# CH32V103R-R1.net
KiCad netlist of a schematic drawn in Altium Designer
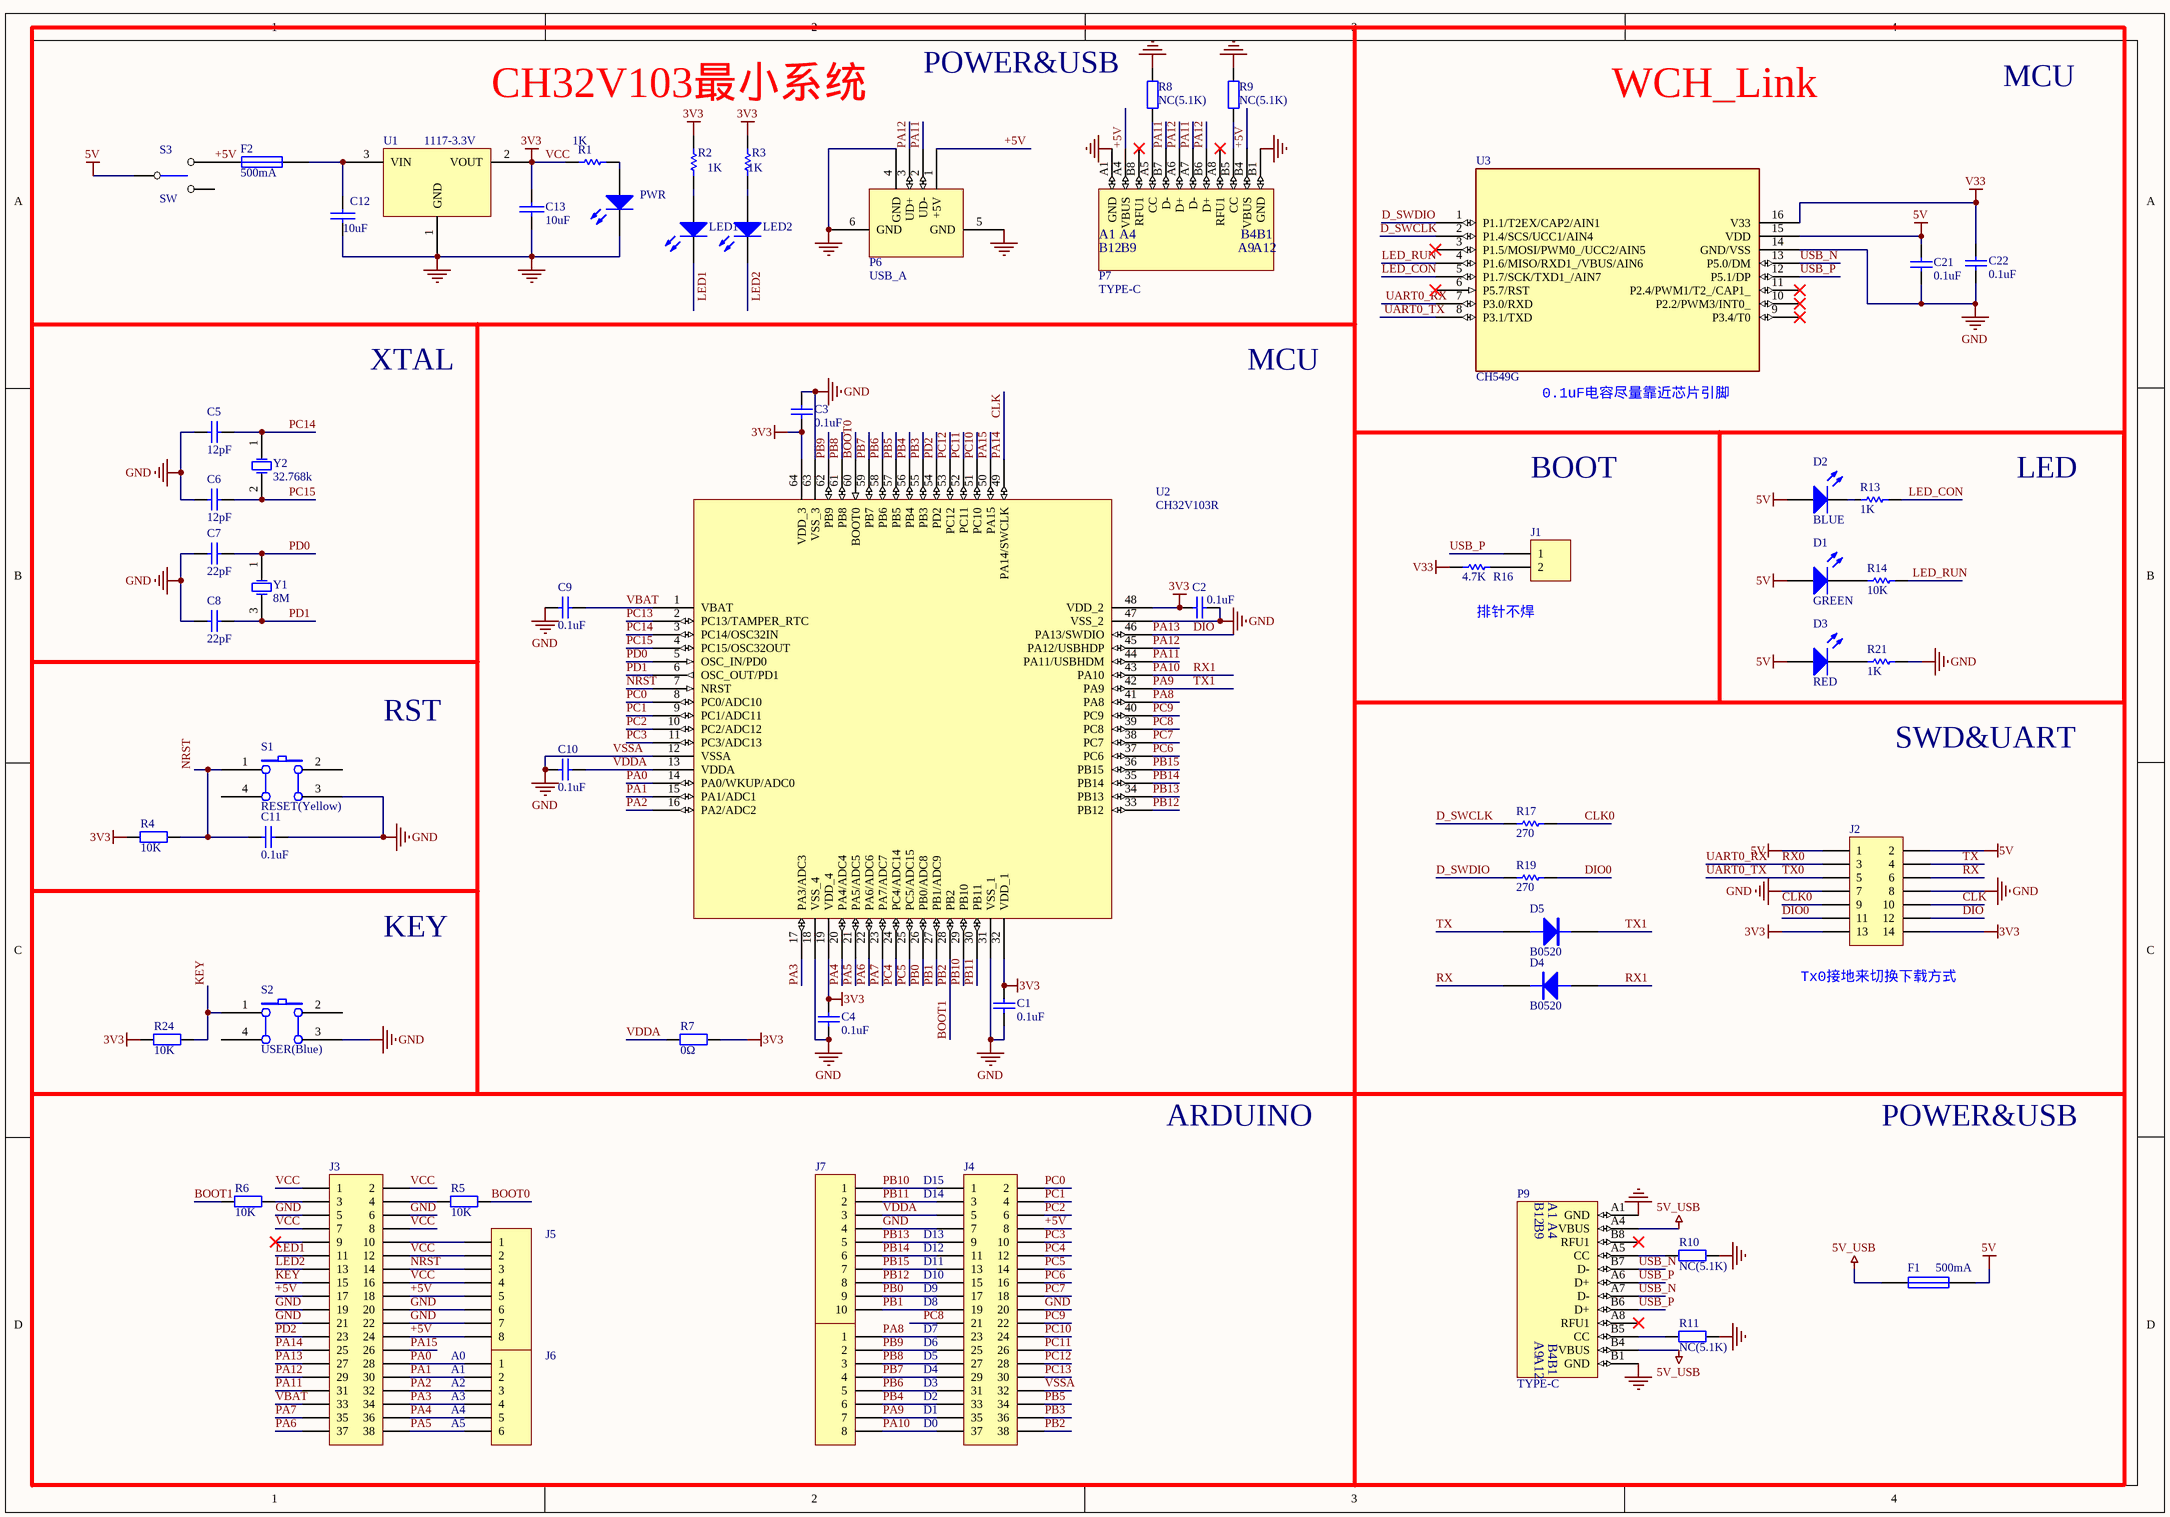
[diagram p0: CH32V103R-R1.SchDoc]

(export (version "E")
  (design (tool "Eeschema 10.0.6"))
  (components
    (comp (ref "C1")
      (value "0.1uF")
      (footprint "0603_C")
      (description "Capacitor")
      (libsource (lib "Miscellaneous Devices") (part "Cap"))
    )
    (comp (ref "C2")
      (value "0.1uF")
      (footprint "0603_C")
      (description "Capacitor")
      (libsource (lib "Miscellaneous Devices") (part "Cap"))
    )
    (comp (ref "C3")
      (value "0.1uF")
      (footprint "0603_C")
      (description "Capacitor")
      (libsource (lib "Miscellaneous Devices") (part "Cap"))
    )
    (comp (ref "C4")
      (value "0.1uF")
      (footprint "0603_C")
      (description "Capacitor")
      (libsource (lib "Miscellaneous Devices") (part "Cap"))
    )
    (comp (ref "C5")
      (value "12pF")
      (footprint "0603_C")
      (description "Capacitor")
      (libsource (lib "Miscellaneous Devices") (part "Cap"))
    )
    (comp (ref "C6")
      (value "12pF")
      (footprint "0603_C")
      (description "Capacitor")
      (libsource (lib "Miscellaneous Devices") (part "Cap"))
    )
    (comp (ref "C7")
      (value "22pF")
      (footprint "0603_C")
      (description "Capacitor")
      (libsource (lib "Miscellaneous Devices") (part "Cap"))
    )
    (comp (ref "C8")
      (value "22pF")
      (footprint "0603_C")
      (description "Capacitor")
      (libsource (lib "Miscellaneous Devices") (part "Cap"))
    )
    (comp (ref "C9")
      (value "0.1uF")
      (footprint "0603_C")
      (description "Capacitor")
      (libsource (lib "Miscellaneous Devices") (part "Cap"))
    )
    (comp (ref "C10")
      (value "0.1uF")
      (footprint "0603_C")
      (description "Capacitor")
      (libsource (lib "Miscellaneous Devices") (part "Cap"))
    )
    (comp (ref "C11")
      (value "0.1uF")
      (footprint "0603_C")
      (description "Capacitor")
      (libsource (lib "Miscellaneous Devices") (part "Cap"))
    )
    (comp (ref "C12")
      (value "10uF")
      (footprint "3216_C")
      (description "Capacitor")
      (libsource (lib "*") (part "CAP"))
    )
    (comp (ref "C13")
      (value "10uF")
      (footprint "0603_C")
      (description "Capacitor")
      (libsource (lib "*") (part "CAP"))
    )
    (comp (ref "C21")
      (value "0.1uF")
      (footprint "0603_C")
      (description "Capacitor")
      (fields (field (name "PUBLISHER") "Altium Limited"))
      (libsource (lib "MYLIB") (part "C-RAD-0603"))
    )
    (comp (ref "C22")
      (value "0.1uF")
      (footprint "0603_C")
      (description "Capacitor")
      (fields (field (name "PUBLISHER") "Altium Limited"))
      (libsource (lib "MYLIB") (part "C-RAD-0603"))
    )
    (comp (ref "D1")
      (value "GREEN")
      (footprint "0603+")
      (description "Typical RED, GREEN, YELLOW, AMBER GaAs LED")
      (fields (field (name "PUBLISHER") "Altium Limited"))
      (libsource (lib "MYLIB") (part "D0603"))
    )
    (comp (ref "D2")
      (value "BLUE")
      (footprint "0603+")
      (description "Typical RED, GREEN, YELLOW, AMBER GaAs LED")
      (fields (field (name "PUBLISHER") "Altium Limited"))
      (libsource (lib "MYLIB") (part "D0603"))
    )
    (comp (ref "D3")
      (value "RED")
      (footprint "0603+")
      (description "Typical RED, GREEN, YELLOW, AMBER GaAs LED")
      (fields (field (name "PUBLISHER") "Altium Limited"))
      (libsource (lib "MYLIB") (part "D0603"))
    )
    (comp (ref "D4")
      (value "B0520")
      (footprint "SOD-323")
      (description "Diode")
      (libsource (lib "*") (part "DIODE"))
    )
    (comp (ref "D5")
      (value "B0520")
      (footprint "SOD-323")
      (description "Diode")
      (libsource (lib "*") (part "DIODE"))
    )
    (comp (ref "F1")
      (value "500mA")
      (footprint "0805")
      (description "Fuse")
      (libsource (lib "*") (part "FUSE1"))
    )
    (comp (ref "F2")
      (value "500mA")
      (footprint "0805")
      (description "Fuse")
      (libsource (lib "*") (part "FUSE1"))
    )
    (comp (ref "J1")
      (value "Header 2")
      (footprint "SIP2-2.54MM")
      (description "Header, 2-Pin")
      (fields (field (name "PUBLISHER") "Altium Limited"))
      (libsource (lib "Miscellaneous Connectors") (part "Header 2"))
    )
    (comp (ref "J2")
      (value "Header 7X2")
      (footprint "IDC14-2.54mm")
      (description "Header, 7-Pin, Dual row")
      (fields (field (name "PUBLISHER") "Altium Limited"))
      (libsource (lib "Miscellaneous Connectors") (part "Header 7X2"))
    )
    (comp (ref "J3")
      (value "Header 19X2")
      (footprint "IDC38-2.54mm")
      (description "Header, 19-Pin, Dual row")
      (fields (field (name "PUBLISHER") "Altium Limited"))
      (libsource (lib "Miscellaneous Connectors") (part "Header 19X2"))
    )
    (comp (ref "J4")
      (value "Header 19X2")
      (footprint "IDC38-2.54mm")
      (description "Header, 19-Pin, Dual row")
      (fields (field (name "PUBLISHER") "Altium Limited"))
      (libsource (lib "Miscellaneous Connectors") (part "Header 19X2"))
    )
    (comp (ref "J5")
      (value "Header 8")
      (footprint "SIP8-2.54mm")
      (description "Header, 8-Pin")
      (fields (field (name "PUBLISHER") "Altium Limited"))
      (libsource (lib "Miscellaneous Connectors") (part "Header 8"))
    )
    (comp (ref "J6")
      (value "Header 6")
      (footprint "SIP6-2.54MM")
      (description "Header, 6-Pin")
      (fields (field (name "PUBLISHER") "Altium Limited"))
      (libsource (lib "Miscellaneous Connectors") (part "Header 6"))
    )
    (comp (ref "J7")
      (value "Header 10")
      (footprint "SIP10-2.54mm")
      (description "Header, 10-Pin")
      (fields (field (name "PUBLISHER") "Altium Limited"))
      (libsource (lib "Miscellaneous Connectors") (part "Header 10"))
    )
    (comp (ref "J8")
      (value "Header 8")
      (footprint "SIP8-2.54mm")
      (description "Header, 8-Pin")
      (fields (field (name "PUBLISHER") "Altium Limited"))
      (libsource (lib "") (part "Header 8_1"))
    )
    (comp (ref "LED1")
      (value "LED1   blue")
      (footprint "0603+")
      (description "Typical INFRARED GaAs LED")
      (fields (field (name "PUBLISHER") "Altium Limited"))
      (libsource (lib "Miscellaneous Devices") (part "LED0"))
    )
    (comp (ref "LED2")
      (value "LED2  blue")
      (footprint "0603+")
      (description "Typical INFRARED GaAs LED")
      (fields (field (name "PUBLISHER") "Altium Limited"))
      (libsource (lib "Miscellaneous Devices") (part "LED0"))
    )
    (comp (ref "P6")
      (value "USB_A")
      (footprint "USBAF")
      (description "USB Port")
      (libsource (lib "CHXXXSCH") (part "USB"))
    )
    (comp (ref "P7")
      (value "TYPE-C")
      (footprint "TYPE-C-Receptacle-2.0")
      (libsource (lib "*") (part "TYPE-C1"))
    )
    (comp (ref "P9")
      (value "TYPE-C")
      (footprint "TYPE-C-Receptacle-2.0")
      (libsource (lib "") (part "TYPE-C1_1"))
    )
    (comp (ref "PWR")
      (value "POWER  red")
      (footprint "0603+")
      (description "Typical INFRARED GaAs LED")
      (fields (field (name "PUBLISHER") "Altium Limited"))
      (libsource (lib "Miscellaneous Devices") (part "LED0"))
    )
    (comp (ref "R1")
      (value "1K")
      (footprint "0603")
      (description "Semiconductor Resistor")
      (libsource (lib "Miscellaneous Devices") (part "Res Semi"))
    )
    (comp (ref "R2")
      (value "1K")
      (footprint "0603")
      (description "Semiconductor Resistor")
      (libsource (lib "Miscellaneous Devices") (part "Res Semi"))
    )
    (comp (ref "R3")
      (value "1K")
      (footprint "0603")
      (description "Semiconductor Resistor")
      (libsource (lib "Miscellaneous Devices") (part "Res Semi"))
    )
    (comp (ref "R4")
      (value "10K")
      (footprint "0603")
      (description "Resistor")
      (libsource (lib "Miscellaneous Devices") (part "Res2"))
    )
    (comp (ref "R5")
      (value "10K")
      (footprint "0603")
      (description "Resistor")
      (libsource (lib "") (part "Res2_1"))
    )
    (comp (ref "R6")
      (value "10K")
      (footprint "0603")
      (description "Resistor")
      (libsource (lib "") (part "Res2_1"))
    )
    (comp (ref "R7")
      (value "0Ω")
      (footprint "0603")
      (description "Resistor")
      (libsource (lib "Miscellaneous Devices") (part "Res2"))
    )
    (comp (ref "R8")
      (value "NC(5.1K)")
      (footprint "0603")
      (description "Resistor")
      (libsource (lib "") (part "Res2_2"))
    )
    (comp (ref "R9")
      (value "NC(5.1K)")
      (footprint "0603")
      (description "Resistor")
      (libsource (lib "") (part "Res2_2"))
    )
    (comp (ref "R10")
      (value "NC(5.1K)")
      (footprint "0603")
      (description "Resistor")
      (libsource (lib "") (part "Res2_1"))
    )
    (comp (ref "R11")
      (value "NC(5.1K)")
      (footprint "0603")
      (description "Resistor")
      (libsource (lib "") (part "Res2_1"))
    )
    (comp (ref "R13")
      (value "1K")
      (footprint "0603")
      (description "Resistor")
      (fields (field (name "PUBLISHER") "Altium Limited"))
      (libsource (lib "MYLIB") (part "0603-1"))
    )
    (comp (ref "R14")
      (value "10K")
      (footprint "0603")
      (description "Resistor")
      (fields (field (name "PUBLISHER") "Altium Limited"))
      (libsource (lib "MYLIB") (part "0603-1"))
    )
    (comp (ref "R16")
      (value "4.7K")
      (footprint "0603")
      (description "Resistor")
      (fields (field (name "PUBLISHER") "Altium Limited"))
      (libsource (lib "MYLIB") (part "0603-1"))
    )
    (comp (ref "R17")
      (value "270")
      (footprint "0603")
      (description "Resistor")
      (fields (field (name "PUBLISHER") "Altium Limited"))
      (libsource (lib "MYLIB") (part "0603-1"))
    )
    (comp (ref "R19")
      (value "270")
      (footprint "0603")
      (description "Resistor")
      (fields (field (name "PUBLISHER") "Altium Limited"))
      (libsource (lib "MYLIB") (part "0603-1"))
    )
    (comp (ref "R21")
      (value "1K")
      (footprint "0603")
      (description "Resistor")
      (fields (field (name "PUBLISHER") "Altium Limited"))
      (libsource (lib "MYLIB") (part "0603-1"))
    )
    (comp (ref "R24")
      (value "10K")
      (footprint "0603")
      (description "Resistor")
      (libsource (lib "Miscellaneous Devices") (part "Res2"))
    )
    (comp (ref "S1")
      (value "RESET(Yellow)")
      (footprint "KEYX")
      (description "SE PUSHBUTTON")
      (libsource (lib "Documents") (part "SW PUSHBUTTON"))
    )
    (comp (ref "S2")
      (value "USER(Blue)")
      (footprint "KEYX")
      (description "SE PUSHBUTTON")
      (libsource (lib "Documents") (part "SW PUSHBUTTON"))
    )
    (comp (ref "S3") (value "SW") (footprint "KEY2") (libsource (lib "MYSCH") (part "SW")))
    (comp (ref "U1")
      (value "1117-3.3V")
      (footprint "SOT-223")
      (libsource (lib "wch_sch_others") (part "1117-3.3V"))
    )
    (comp (ref "U2")
      (value "CH32V103R")
      (footprint "LQFP64M_10X10")
      (description "RISC-V MCU with USB device & USB host & ADC & Touch Key")
      (libsource (lib "CHXXX(1)") (part "CH32V103R"))
    )
    (comp (ref "U3")
      (value "CH549G")
      (footprint "SOP16")
      (description "8bit MCS51 MCU with ADC & USB type-C host & device & dual UART & SPI")
      (libsource (lib "CHXXXSCH(1)") (part "CH549G"))
    )
    (comp (ref "Y1")
      (value "8M")
      (footprint "XT3225")
      (description "Crystal Oscillator")
      (fields (field (name "PUBLISHER") "Altium Limited"))
      (libsource (lib "Miscellaneous Devices") (part "XTAL"))
    )
    (comp (ref "Y2")
      (value "32.768k")
      (footprint "FC-135")
      (description "Crystal Oscillator")
      (fields (field (name "PUBLISHER") "Altium Limited"))
      (libsource (lib "") (part "XTAL_1"))
    )
  )
  (nets
    (net (code "1") (name "/+5V") (class "Default")
      (node (ref "F2") (pin "1") (pinfunction "1_1") (pintype "passive"))
      (node (ref "J3") (pin "17") (pinfunction "17_17") (pintype "passive"))
      (node (ref "J3") (pin "18") (pinfunction "18_18") (pintype "passive"))
      (node (ref "J3") (pin "24") (pinfunction "24_24") (pintype "passive"))
      (node (ref "J4") (pin "8") (pinfunction "8_8") (pintype "passive"))
      (node (ref "J5") (pin "5") (pinfunction "5_5") (pintype "passive"))
      (node (ref "J5") (pin "8") (pinfunction "8_8") (pintype "passive"))
      (node (ref "P6") (pin "1") (pinfunction "+5V_1") (pintype "power_in"))
      (node (ref "P7") (pin "A4") (pinfunction "VBUS_A4") (pintype "bidirectional"))
      (node (ref "P7") (pin "B4") (pinfunction "VBUS_B4") (pintype "bidirectional"))
      (node (ref "S3") (pin "3") (pinfunction "3_3") (pintype "passive"))
    )
    (net (code "3") (name "/BOOT0") (class "Default")
      (node (ref "R5") (pin "2") (pinfunction "2_2") (pintype "passive"))
      (node (ref "U2") (pin "60") (pinfunction "BOOT0_60") (pintype "input"))
    )
    (net (code "4") (name "/BOOT1") (class "Default")
      (node (ref "J4") (pin "38") (pinfunction "38_38") (pintype "passive"))
      (node (ref "R6") (pin "1") (pinfunction "1_1") (pintype "passive"))
      (node (ref "U2") (pin "28") (pinfunction "PB2_28") (pintype "bidirectional"))
    )
    (net (code "5") (name "/CLK") (class "Default")
      (node (ref "J2") (pin "10") (pinfunction "10_10") (pintype "passive"))
      (node (ref "J3") (pin "25") (pinfunction "25_25") (pintype "passive"))
      (node (ref "U2") (pin "49") (pinfunction "PA14/SWCLK_49") (pintype "bidirectional"))
    )
    (net (code "6") (name "/CLK0") (class "Default")
      (node (ref "J2") (pin "9") (pinfunction "9_9") (pintype "passive"))
      (node (ref "R17") (pin "1") (pinfunction "1_1") (pintype "passive"))
    )
    (net (code "7") (name "/DIO") (class "Default")
      (node (ref "J2") (pin "12") (pinfunction "12_12") (pintype "passive"))
      (node (ref "J3") (pin "27") (pinfunction "27_27") (pintype "passive"))
      (node (ref "U2") (pin "46") (pinfunction "PA13/SWDIO_46") (pintype "bidirectional"))
    )
    (net (code "8") (name "/DIO0") (class "Default")
      (node (ref "J2") (pin "11") (pinfunction "11_11") (pintype "passive"))
      (node (ref "R19") (pin "1") (pinfunction "1_1") (pintype "passive"))
    )
    (net (code "9") (name "/D_SWCLK") (class "Default")
      (node (ref "R17") (pin "2") (pinfunction "2_2") (pintype "passive"))
      (node (ref "U3") (pin "2") (pinfunction "P1.4/SCS/UCC1/AIN4_2") (pintype "bidirectional"))
    )
    (net (code "10") (name "/D_SWDIO") (class "Default")
      (node (ref "R19") (pin "2") (pinfunction "2_2") (pintype "passive"))
      (node (ref "U3") (pin "1") (pinfunction "P1.1/T2EX/CAP2/AIN1_1") (pintype "bidirectional"))
    )
    (net (code "11") (name "/KEY") (class "Default")
      (node (ref "J3") (pin "15") (pinfunction "15_15") (pintype "passive"))
      (node (ref "R24") (pin "1") (pinfunction "1_1") (pintype "passive"))
      (node (ref "S2") (pin "1") (pinfunction "A0_1") (pintype "passive"))
    )
    (net (code "12") (name "/LED1") (class "Default")
      (node (ref "J3") (pin "11") (pinfunction "11_11") (pintype "passive"))
      (node (ref "LED1") (pin "2") (pinfunction "K_2") (pintype "passive"))
    )
    (net (code "13") (name "/LED2") (class "Default")
      (node (ref "J3") (pin "13") (pinfunction "13_13") (pintype "passive"))
      (node (ref "LED2") (pin "2") (pinfunction "K_2") (pintype "passive"))
    )
    (net (code "14") (name "/LED_CON") (class "Default")
      (node (ref "R13") (pin "1") (pinfunction "1_1") (pintype "passive"))
      (node (ref "U3") (pin "5") (pinfunction "P1.7/SCK/TXD1_/AIN7_5") (pintype "bidirectional"))
    )
    (net (code "15") (name "/LED_RUN") (class "Default")
      (node (ref "R14") (pin "1") (pinfunction "1_1") (pintype "passive"))
      (node (ref "U3") (pin "4") (pinfunction "P1.6/MISO/RXD1_/VBUS/AIN6_4") (pintype "bidirectional"))
    )
    (net (code "16") (name "/NRST") (class "Default")
      (node (ref "C11") (pin "2") (pinfunction "2_2") (pintype "passive"))
      (node (ref "J3") (pin "14") (pinfunction "14_14") (pintype "passive"))
      (node (ref "J5") (pin "3") (pinfunction "3_3") (pintype "passive"))
      (node (ref "R4") (pin "1") (pinfunction "1_1") (pintype "passive"))
      (node (ref "S1") (pin "1") (pinfunction "A0_1") (pintype "passive"))
      (node (ref "U2") (pin "7") (pinfunction "NRST_7") (pintype "input"))
    )
    (net (code "17") (name "/PA0") (class "Default")
      (node (ref "J3") (pin "28") (pinfunction "28_28") (pintype "passive"))
      (node (ref "J6") (pin "1") (pinfunction "1_1") (pintype "passive"))
      (node (ref "U2") (pin "14") (pinfunction "PA0/WKUP/ADC0_14") (pintype "bidirectional"))
    )
    (net (code "18") (name "/PA1") (class "Default")
      (node (ref "J3") (pin "30") (pinfunction "30_30") (pintype "passive"))
      (node (ref "J6") (pin "2") (pinfunction "2_2") (pintype "passive"))
      (node (ref "U2") (pin "15") (pinfunction "PA1/ADC1_15") (pintype "bidirectional"))
    )
    (net (code "19") (name "/PA2") (class "Default")
      (node (ref "J3") (pin "32") (pinfunction "32_32") (pintype "passive"))
      (node (ref "J6") (pin "3") (pinfunction "3_3") (pintype "passive"))
      (node (ref "U2") (pin "16") (pinfunction "PA2/ADC2_16") (pintype "bidirectional"))
    )
    (net (code "20") (name "/PA3") (class "Default")
      (node (ref "J3") (pin "34") (pinfunction "34_34") (pintype "passive"))
      (node (ref "J6") (pin "4") (pinfunction "4_4") (pintype "passive"))
      (node (ref "U2") (pin "17") (pinfunction "PA3/ADC3_17") (pintype "bidirectional"))
    )
    (net (code "21") (name "/PA4") (class "Default")
      (node (ref "J3") (pin "36") (pinfunction "36_36") (pintype "passive"))
      (node (ref "J6") (pin "5") (pinfunction "5_5") (pintype "passive"))
      (node (ref "U2") (pin "20") (pinfunction "PA4/ADC4_20") (pintype "bidirectional"))
    )
    (net (code "22") (name "/PA5") (class "Default")
      (node (ref "J3") (pin "38") (pinfunction "38_38") (pintype "passive"))
      (node (ref "J6") (pin "6") (pinfunction "6_6") (pintype "passive"))
      (node (ref "U2") (pin "21") (pinfunction "PA5/ADC5_21") (pintype "bidirectional"))
    )
    (net (code "23") (name "/PA6") (class "Default")
      (node (ref "J3") (pin "37") (pinfunction "37_37") (pintype "passive"))
      (node (ref "U2") (pin "22") (pinfunction "PA6/ADC6_22") (pintype "bidirectional"))
    )
    (net (code "24") (name "/PA7") (class "Default")
      (node (ref "J3") (pin "35") (pinfunction "35_35") (pintype "passive"))
      (node (ref "U2") (pin "23") (pinfunction "PA7/ADC7_23") (pintype "bidirectional"))
    )
    (net (code "25") (name "/PA8") (class "Default")
      (node (ref "J4") (pin "23") (pinfunction "23_23") (pintype "passive"))
      (node (ref "J8") (pin "1") (pinfunction "1_1") (pintype "passive"))
      (node (ref "U2") (pin "41") (pinfunction "PA8_41") (pintype "bidirectional"))
    )
    (net (code "26") (name "/PA9") (class "Default")
      (node (ref "D5") (pin "2") (pinfunction "K_2") (pintype "passive"))
      (node (ref "J4") (pin "35") (pinfunction "35_35") (pintype "passive"))
      (node (ref "J8") (pin "7") (pinfunction "7_7") (pintype "passive"))
      (node (ref "U2") (pin "42") (pinfunction "PA9_42") (pintype "bidirectional"))
    )
    (net (code "27") (name "/PA10") (class "Default")
      (node (ref "D4") (pin "1") (pinfunction "A_1") (pintype "passive"))
      (node (ref "J4") (pin "37") (pinfunction "37_37") (pintype "passive"))
      (node (ref "J8") (pin "8") (pinfunction "8_8") (pintype "passive"))
      (node (ref "U2") (pin "43") (pinfunction "PA10_43") (pintype "bidirectional"))
    )
    (net (code "28") (name "/PA11") (class "Default")
      (node (ref "J3") (pin "31") (pinfunction "31_31") (pintype "passive"))
      (node (ref "P6") (pin "2") (pinfunction "UD-_2") (pintype "bidirectional"))
      (node (ref "P7") (pin "A7") (pinfunction "D-_A7") (pintype "bidirectional"))
      (node (ref "P7") (pin "B7") (pinfunction "D-_B7") (pintype "bidirectional"))
      (node (ref "U2") (pin "44") (pinfunction "PA11/USBHDM_44") (pintype "bidirectional"))
    )
    (net (code "29") (name "/PA12") (class "Default")
      (node (ref "J3") (pin "29") (pinfunction "29_29") (pintype "passive"))
      (node (ref "P6") (pin "3") (pinfunction "UD+_3") (pintype "bidirectional"))
      (node (ref "P7") (pin "A6") (pinfunction "D+_A6") (pintype "bidirectional"))
      (node (ref "P7") (pin "B6") (pinfunction "D+_B6") (pintype "bidirectional"))
      (node (ref "U2") (pin "45") (pinfunction "PA12/USBHDP_45") (pintype "bidirectional"))
    )
    (net (code "30") (name "/PA15") (class "Default")
      (node (ref "J3") (pin "26") (pinfunction "26_26") (pintype "passive"))
      (node (ref "U2") (pin "50") (pinfunction "PA15_50") (pintype "bidirectional"))
    )
    (net (code "31") (name "/PB0") (class "Default")
      (node (ref "J4") (pin "17") (pinfunction "17_17") (pintype "passive"))
      (node (ref "J7") (pin "9") (pinfunction "9_9") (pintype "passive"))
      (node (ref "U2") (pin "26") (pinfunction "PB0/ADC8_26") (pintype "bidirectional"))
    )
    (net (code "32") (name "/PB1") (class "Default")
      (node (ref "J4") (pin "19") (pinfunction "19_19") (pintype "passive"))
      (node (ref "J7") (pin "10") (pinfunction "10_10") (pintype "passive"))
      (node (ref "U2") (pin "27") (pinfunction "PB1/ADC9_27") (pintype "bidirectional"))
    )
    (net (code "33") (name "/PB3") (class "Default")
      (node (ref "J4") (pin "36") (pinfunction "36_36") (pintype "passive"))
      (node (ref "U2") (pin "55") (pinfunction "PB3_55") (pintype "bidirectional"))
    )
    (net (code "34") (name "/PB4") (class "Default")
      (node (ref "J4") (pin "33") (pinfunction "33_33") (pintype "passive"))
      (node (ref "J8") (pin "6") (pinfunction "6_6") (pintype "passive"))
      (node (ref "U2") (pin "56") (pinfunction "PB4_56") (pintype "bidirectional"))
    )
    (net (code "35") (name "/PB5") (class "Default")
      (node (ref "J4") (pin "34") (pinfunction "34_34") (pintype "passive"))
      (node (ref "U2") (pin "57") (pinfunction "PB5_57") (pintype "bidirectional"))
    )
    (net (code "36") (name "/PB6") (class "Default")
      (node (ref "J4") (pin "31") (pinfunction "31_31") (pintype "passive"))
      (node (ref "J8") (pin "5") (pinfunction "5_5") (pintype "passive"))
      (node (ref "U2") (pin "58") (pinfunction "PB6_58") (pintype "bidirectional"))
    )
    (net (code "37") (name "/PB7") (class "Default")
      (node (ref "J4") (pin "29") (pinfunction "29_29") (pintype "passive"))
      (node (ref "J8") (pin "4") (pinfunction "4_4") (pintype "passive"))
      (node (ref "U2") (pin "59") (pinfunction "PB7_59") (pintype "bidirectional"))
    )
    (net (code "38") (name "/PB8") (class "Default")
      (node (ref "J4") (pin "27") (pinfunction "27_27") (pintype "passive"))
      (node (ref "J8") (pin "3") (pinfunction "3_3") (pintype "passive"))
      (node (ref "U2") (pin "61") (pinfunction "PB8_61") (pintype "bidirectional"))
    )
    (net (code "39") (name "/PB9") (class "Default")
      (node (ref "J4") (pin "25") (pinfunction "25_25") (pintype "passive"))
      (node (ref "J8") (pin "2") (pinfunction "2_2") (pintype "passive"))
      (node (ref "U2") (pin "62") (pinfunction "PB9_62") (pintype "bidirectional"))
    )
    (net (code "40") (name "/PB10") (class "Default")
      (node (ref "J4") (pin "1") (pinfunction "1_1") (pintype "passive"))
      (node (ref "J7") (pin "1") (pinfunction "1_1") (pintype "passive"))
      (node (ref "U2") (pin "29") (pinfunction "PB10_29") (pintype "bidirectional"))
    )
    (net (code "41") (name "/PB11") (class "Default")
      (node (ref "J4") (pin "3") (pinfunction "3_3") (pintype "passive"))
      (node (ref "J7") (pin "2") (pinfunction "2_2") (pintype "passive"))
      (node (ref "U2") (pin "30") (pinfunction "PB11_30") (pintype "bidirectional"))
    )
    (net (code "42") (name "/PB12") (class "Default")
      (node (ref "J4") (pin "15") (pinfunction "15_15") (pintype "passive"))
      (node (ref "J7") (pin "8") (pinfunction "8_8") (pintype "passive"))
      (node (ref "U2") (pin "33") (pinfunction "PB12_33") (pintype "bidirectional"))
    )
    (net (code "43") (name "/PB13") (class "Default")
      (node (ref "J4") (pin "9") (pinfunction "9_9") (pintype "passive"))
      (node (ref "J7") (pin "5") (pinfunction "5_5") (pintype "passive"))
      (node (ref "U2") (pin "34") (pinfunction "PB13_34") (pintype "bidirectional"))
    )
    (net (code "44") (name "/PB14") (class "Default")
      (node (ref "J4") (pin "11") (pinfunction "11_11") (pintype "passive"))
      (node (ref "J7") (pin "6") (pinfunction "6_6") (pintype "passive"))
      (node (ref "U2") (pin "35") (pinfunction "PB14_35") (pintype "bidirectional"))
    )
    (net (code "45") (name "/PB15") (class "Default")
      (node (ref "J4") (pin "13") (pinfunction "13_13") (pintype "passive"))
      (node (ref "J7") (pin "7") (pinfunction "7_7") (pintype "passive"))
      (node (ref "U2") (pin "36") (pinfunction "PB15_36") (pintype "bidirectional"))
    )
    (net (code "46") (name "/PC0") (class "Default")
      (node (ref "J4") (pin "2") (pinfunction "2_2") (pintype "passive"))
      (node (ref "U2") (pin "8") (pinfunction "PC0/ADC10_8") (pintype "bidirectional"))
    )
    (net (code "47") (name "/PC1") (class "Default")
      (node (ref "J4") (pin "4") (pinfunction "4_4") (pintype "passive"))
      (node (ref "U2") (pin "9") (pinfunction "PC1/ADC11_9") (pintype "bidirectional"))
    )
    (net (code "48") (name "/PC2") (class "Default")
      (node (ref "J4") (pin "6") (pinfunction "6_6") (pintype "passive"))
      (node (ref "U2") (pin "10") (pinfunction "PC2/ADC12_10") (pintype "bidirectional"))
    )
    (net (code "49") (name "/PC3") (class "Default")
      (node (ref "J4") (pin "10") (pinfunction "10_10") (pintype "passive"))
      (node (ref "U2") (pin "11") (pinfunction "PC3/ADC13_11") (pintype "bidirectional"))
    )
    (net (code "50") (name "/PC4") (class "Default")
      (node (ref "J4") (pin "12") (pinfunction "12_12") (pintype "passive"))
      (node (ref "U2") (pin "24") (pinfunction "PC4/ADC14_24") (pintype "bidirectional"))
    )
    (net (code "51") (name "/PC5") (class "Default")
      (node (ref "J4") (pin "14") (pinfunction "14_14") (pintype "passive"))
      (node (ref "U2") (pin "25") (pinfunction "PC5/ADC15_25") (pintype "bidirectional"))
    )
    (net (code "52") (name "/PC6") (class "Default")
      (node (ref "J4") (pin "16") (pinfunction "16_16") (pintype "passive"))
      (node (ref "U2") (pin "37") (pinfunction "PC6_37") (pintype "bidirectional"))
    )
    (net (code "53") (name "/PC7") (class "Default")
      (node (ref "J4") (pin "18") (pinfunction "18_18") (pintype "passive"))
      (node (ref "U2") (pin "38") (pinfunction "PC7_38") (pintype "bidirectional"))
    )
    (net (code "54") (name "/PC8") (class "Default")
      (node (ref "J4") (pin "21") (pinfunction "21_21") (pintype "passive"))
      (node (ref "U2") (pin "39") (pinfunction "PC8_39") (pintype "bidirectional"))
    )
    (net (code "55") (name "/PC9") (class "Default")
      (node (ref "J4") (pin "22") (pinfunction "22_22") (pintype "passive"))
      (node (ref "U2") (pin "40") (pinfunction "PC9_40") (pintype "bidirectional"))
    )
    (net (code "56") (name "/PC10") (class "Default")
      (node (ref "J4") (pin "24") (pinfunction "24_24") (pintype "passive"))
      (node (ref "U2") (pin "51") (pinfunction "PC10_51") (pintype "bidirectional"))
    )
    (net (code "57") (name "/PC11") (class "Default")
      (node (ref "J4") (pin "26") (pinfunction "26_26") (pintype "passive"))
      (node (ref "U2") (pin "52") (pinfunction "PC11_52") (pintype "bidirectional"))
    )
    (net (code "58") (name "/PC12") (class "Default")
      (node (ref "J4") (pin "28") (pinfunction "28_28") (pintype "passive"))
      (node (ref "U2") (pin "53") (pinfunction "PC12_53") (pintype "bidirectional"))
    )
    (net (code "59") (name "/PC13") (class "Default")
      (node (ref "J4") (pin "30") (pinfunction "30_30") (pintype "passive"))
      (node (ref "U2") (pin "2") (pinfunction "PC13/TAMPER_RTC_2") (pintype "bidirectional"))
    )
    (net (code "60") (name "/PC14") (class "Default")
      (node (ref "C5") (pin "1") (pinfunction "1_1") (pintype "passive"))
      (node (ref "U2") (pin "3") (pinfunction "PC14/OSC32IN_3") (pintype "bidirectional"))
      (node (ref "Y2") (pin "1") (pinfunction "OSC1_1") (pintype "passive"))
    )
    (net (code "61") (name "/PC15") (class "Default")
      (node (ref "C6") (pin "1") (pinfunction "1_1") (pintype "passive"))
      (node (ref "U2") (pin "4") (pinfunction "PC15/OSC32OUT_4") (pintype "bidirectional"))
      (node (ref "Y2") (pin "2") (pinfunction "OSC2_2") (pintype "passive"))
    )
    (net (code "62") (name "/PD0") (class "Default")
      (node (ref "C7") (pin "2") (pinfunction "2_2") (pintype "passive"))
      (node (ref "U2") (pin "5") (pinfunction "OSC_IN/PD0_5") (pintype "input"))
      (node (ref "Y1") (pin "1") (pinfunction "OSC1_1") (pintype "passive"))
    )
    (net (code "63") (name "/PD1") (class "Default")
      (node (ref "C8") (pin "2") (pinfunction "2_2") (pintype "passive"))
      (node (ref "U2") (pin "6") (pinfunction "OSC_OUT/PD1_6") (pintype "output"))
      (node (ref "Y1") (pin "3") (pinfunction "OSC2_3") (pintype "passive"))
    )
    (net (code "64") (name "/PD2") (class "Default")
      (node (ref "J3") (pin "23") (pinfunction "23_23") (pintype "passive"))
      (node (ref "U2") (pin "54") (pinfunction "PD2_54") (pintype "bidirectional"))
    )
    (net (code "65") (name "/RX") (class "Default")
      (node (ref "D4") (pin "2") (pinfunction "K_2") (pintype "passive"))
      (node (ref "J2") (pin "6") (pinfunction "6_6") (pintype "passive"))
    )
    (net (code "66") (name "/RX0") (class "Default")
      (node (ref "J2") (pin "3") (pinfunction "3_3") (pintype "passive"))
      (node (ref "U3") (pin "7") (pinfunction "P3.0/RXD_7") (pintype "bidirectional"))
    )
    (net (code "67") (name "/TX") (class "Default")
      (node (ref "D5") (pin "1") (pinfunction "A_1") (pintype "passive"))
      (node (ref "J2") (pin "4") (pinfunction "4_4") (pintype "passive"))
    )
    (net (code "68") (name "/TX0") (class "Default")
      (node (ref "J2") (pin "5") (pinfunction "5_5") (pintype "passive"))
      (node (ref "U3") (pin "8") (pinfunction "P3.1/TXD_8") (pintype "bidirectional"))
    )
    (net (code "69") (name "/USB_N") (class "Default")
      (node (ref "P9") (pin "A7") (pinfunction "D-_A7") (pintype "bidirectional"))
      (node (ref "P9") (pin "B7") (pinfunction "D-_B7") (pintype "bidirectional"))
      (node (ref "U3") (pin "13") (pinfunction "P5.0/DM_13") (pintype "bidirectional"))
    )
    (net (code "70") (name "/USB_P") (class "Default")
      (node (ref "J1") (pin "1") (pinfunction "1_1") (pintype "passive"))
      (node (ref "P9") (pin "A6") (pinfunction "D+_A6") (pintype "bidirectional"))
      (node (ref "P9") (pin "B6") (pinfunction "D+_B6") (pintype "bidirectional"))
      (node (ref "U3") (pin "12") (pinfunction "P5.1/DP_12") (pintype "bidirectional"))
    )
    (net (code "71") (name "/VBAT") (class "Default")
      (node (ref "C9") (pin "1") (pinfunction "1_1") (pintype "passive"))
      (node (ref "J3") (pin "33") (pinfunction "33_33") (pintype "passive"))
      (node (ref "U2") (pin "1") (pinfunction "VBAT_1") (pintype "power_in"))
    )
    (net (code "72") (name "/VDDA") (class "Default")
      (node (ref "C10") (pin "1") (pinfunction "1_1") (pintype "passive"))
      (node (ref "J4") (pin "5") (pinfunction "5_5") (pintype "passive"))
      (node (ref "J7") (pin "3") (pinfunction "3_3") (pintype "passive"))
      (node (ref "R7") (pin "2") (pinfunction "2_2") (pintype "passive"))
      (node (ref "U2") (pin "13") (pinfunction "VDDA_13") (pintype "power_in"))
    )
    (net (code "73") (name "3V3") (class "Default")
      (node (ref "C1") (pin "2") (pinfunction "2_2") (pintype "passive"))
      (node (ref "C13") (pin "1") (pinfunction "1_1") (pintype "passive"))
      (node (ref "C2") (pin "2") (pinfunction "2_2") (pintype "passive"))
      (node (ref "C3") (pin "2") (pinfunction "2_2") (pintype "passive"))
      (node (ref "C4") (pin "2") (pinfunction "2_2") (pintype "passive"))
      (node (ref "J2") (pin "13") (pinfunction "13_13") (pintype "passive"))
      (node (ref "J2") (pin "14") (pinfunction "14_14") (pintype "passive"))
      (node (ref "J3") (pin "1") (pinfunction "1_1") (pintype "passive"))
      (node (ref "J3") (pin "12") (pinfunction "12_12") (pintype "passive"))
      (node (ref "J3") (pin "16") (pinfunction "16_16") (pintype "passive"))
      (node (ref "J3") (pin "2") (pinfunction "2_2") (pintype "passive"))
      (node (ref "J3") (pin "7") (pinfunction "7_7") (pintype "passive"))
      (node (ref "J3") (pin "8") (pinfunction "8_8") (pintype "passive"))
      (node (ref "J5") (pin "2") (pinfunction "2_2") (pintype "passive"))
      (node (ref "J5") (pin "4") (pinfunction "4_4") (pintype "passive"))
      (node (ref "R1") (pin "2") (pinfunction "2_2") (pintype "passive"))
      (node (ref "R2") (pin "1") (pinfunction "1_1") (pintype "passive"))
      (node (ref "R24") (pin "2") (pinfunction "2_2") (pintype "passive"))
      (node (ref "R3") (pin "1") (pinfunction "1_1") (pintype "passive"))
      (node (ref "R4") (pin "2") (pinfunction "2_2") (pintype "passive"))
      (node (ref "R7") (pin "1") (pinfunction "1_1") (pintype "passive"))
      (node (ref "U1") (pin "2") (pinfunction "VOUT_2") (pintype "passive"))
      (node (ref "U2") (pin "19") (pinfunction "VDD_4_19") (pintype "power_in"))
      (node (ref "U2") (pin "32") (pinfunction "VDD_1_32") (pintype "power_in"))
      (node (ref "U2") (pin "48") (pinfunction "VDD_2_48") (pintype "power_in"))
      (node (ref "U2") (pin "64") (pinfunction "VDD_3_64") (pintype "power_in"))
    )
    (net (code "74") (name "5V") (class "Default")
      (node (ref "C21") (pin "1") (pinfunction "1_1") (pintype "passive"))
      (node (ref "D1") (pin "1") (pinfunction "A_1") (pintype "passive"))
      (node (ref "D2") (pin "1") (pinfunction "A_1") (pintype "passive"))
      (node (ref "D3") (pin "1") (pinfunction "A_1") (pintype "passive"))
      (node (ref "F1") (pin "2") (pinfunction "2_2") (pintype "passive"))
      (node (ref "J2") (pin "1") (pinfunction "1_1") (pintype "passive"))
      (node (ref "J2") (pin "2") (pinfunction "2_2") (pintype "passive"))
      (node (ref "S3") (pin "1") (pinfunction "1_1") (pintype "passive"))
      (node (ref "U3") (pin "15") (pinfunction "VDD_15") (pintype "power_in"))
    )
    (net (code "75") (name "5V_USB") (class "Default")
      (node (ref "F1") (pin "1") (pinfunction "1_1") (pintype "passive"))
      (node (ref "P9") (pin "A4") (pinfunction "VBUS_A4") (pintype "bidirectional"))
      (node (ref "P9") (pin "B4") (pinfunction "VBUS_B4") (pintype "bidirectional"))
    )
    (net (code "76") (name "GND") (class "Default")
      (node (ref "C1") (pin "1") (pinfunction "1_1") (pintype "passive"))
      (node (ref "C10") (pin "2") (pinfunction "2_2") (pintype "passive"))
      (node (ref "C11") (pin "1") (pinfunction "1_1") (pintype "passive"))
      (node (ref "C12") (pin "2") (pinfunction "2_2") (pintype "passive"))
      (node (ref "C13") (pin "2") (pinfunction "2_2") (pintype "passive"))
      (node (ref "C2") (pin "1") (pinfunction "1_1") (pintype "passive"))
      (node (ref "C21") (pin "2") (pinfunction "2_2") (pintype "passive"))
      (node (ref "C22") (pin "2") (pinfunction "2_2") (pintype "passive"))
      (node (ref "C3") (pin "1") (pinfunction "1_1") (pintype "passive"))
      (node (ref "C4") (pin "1") (pinfunction "1_1") (pintype "passive"))
      (node (ref "C5") (pin "2") (pinfunction "2_2") (pintype "passive"))
      (node (ref "C6") (pin "2") (pinfunction "2_2") (pintype "passive"))
      (node (ref "C7") (pin "1") (pinfunction "1_1") (pintype "passive"))
      (node (ref "C8") (pin "1") (pinfunction "1_1") (pintype "passive"))
      (node (ref "C9") (pin "2") (pinfunction "2_2") (pintype "passive"))
      (node (ref "J2") (pin "7") (pinfunction "7_7") (pintype "passive"))
      (node (ref "J2") (pin "8") (pinfunction "8_8") (pintype "passive"))
      (node (ref "J3") (pin "19") (pinfunction "19_19") (pintype "passive"))
      (node (ref "J3") (pin "20") (pinfunction "20_20") (pintype "passive"))
      (node (ref "J3") (pin "21") (pinfunction "21_21") (pintype "passive"))
      (node (ref "J3") (pin "22") (pinfunction "22_22") (pintype "passive"))
      (node (ref "J3") (pin "5") (pinfunction "5_5") (pintype "passive"))
      (node (ref "J3") (pin "6") (pinfunction "6_6") (pintype "passive"))
      (node (ref "J4") (pin "20") (pinfunction "20_20") (pintype "passive"))
      (node (ref "J4") (pin "32") (pinfunction "32_32") (pintype "passive"))
      (node (ref "J4") (pin "7") (pinfunction "7_7") (pintype "passive"))
      (node (ref "J5") (pin "6") (pinfunction "6_6") (pintype "passive"))
      (node (ref "J5") (pin "7") (pinfunction "7_7") (pintype "passive"))
      (node (ref "J7") (pin "4") (pinfunction "4_4") (pintype "passive"))
      (node (ref "P6") (pin "4") (pinfunction "GND_4") (pintype "power_in"))
      (node (ref "P6") (pin "5") (pinfunction "GND_5") (pintype "power_in"))
      (node (ref "P6") (pin "6") (pinfunction "GND_6") (pintype "power_in"))
      (node (ref "P7") (pin "A1") (pinfunction "GND_A1") (pintype "bidirectional"))
      (node (ref "P7") (pin "B1") (pinfunction "GND_B1") (pintype "bidirectional"))
      (node (ref "P9") (pin "A1") (pinfunction "GND_A1") (pintype "bidirectional"))
      (node (ref "P9") (pin "B1") (pinfunction "GND_B1") (pintype "bidirectional"))
      (node (ref "PWR") (pin "2") (pinfunction "K_2") (pintype "passive"))
      (node (ref "R10") (pin "2") (pinfunction "2_2") (pintype "passive"))
      (node (ref "R11") (pin "2") (pinfunction "2_2") (pintype "passive"))
      (node (ref "R21") (pin "1") (pinfunction "1_1") (pintype "passive"))
      (node (ref "R8") (pin "1") (pinfunction "1_1") (pintype "passive"))
      (node (ref "R9") (pin "1") (pinfunction "1_1") (pintype "passive"))
      (node (ref "S1") (pin "3") (pinfunction "B1_3") (pintype "passive"))
      (node (ref "S2") (pin "3") (pinfunction "B1_3") (pintype "passive"))
      (node (ref "U1") (pin "1") (pinfunction "GND_1") (pintype "passive"))
      (node (ref "U2") (pin "12") (pinfunction "VSSA_12") (pintype "power_in"))
      (node (ref "U2") (pin "18") (pinfunction "VSS_4_18") (pintype "power_in"))
      (node (ref "U2") (pin "31") (pinfunction "VSS_1_31") (pintype "power_in"))
      (node (ref "U2") (pin "47") (pinfunction "VSS_2_47") (pintype "power_in"))
      (node (ref "U2") (pin "63") (pinfunction "VSS_3_63") (pintype "power_in"))
      (node (ref "U3") (pin "14") (pinfunction "GND/VSS_14") (pintype "power_in"))
    )
    (net (code "77") (name "Net-(D1-K)") (class "Default")
      (node (ref "D1") (pin "2") (pinfunction "K_2") (pintype "passive"))
      (node (ref "R14") (pin "2") (pinfunction "2_2") (pintype "passive"))
    )
    (net (code "78") (name "Net-(D2-K)") (class "Default")
      (node (ref "D2") (pin "2") (pinfunction "K_2") (pintype "passive"))
      (node (ref "R13") (pin "2") (pinfunction "2_2") (pintype "passive"))
    )
    (net (code "79") (name "Net-(D3-K)") (class "Default")
      (node (ref "D3") (pin "2") (pinfunction "K_2") (pintype "passive"))
      (node (ref "R21") (pin "2") (pinfunction "2_2") (pintype "passive"))
    )
    (net (code "80") (name "Net-(J1-Pad2)") (class "Default")
      (node (ref "J1") (pin "2") (pinfunction "2_2") (pintype "passive"))
      (node (ref "R16") (pin "1") (pinfunction "1_1") (pintype "passive"))
    )
    (net (code "81") (name "Net-(J3-Pad3)") (class "Default")
      (node (ref "J3") (pin "3") (pinfunction "3_3") (pintype "passive"))
      (node (ref "R6") (pin "2") (pinfunction "2_2") (pintype "passive"))
    )
    (net (code "82") (name "Net-(J3-Pad4)") (class "Default")
      (node (ref "J3") (pin "4") (pinfunction "4_4") (pintype "passive"))
      (node (ref "R5") (pin "1") (pinfunction "1_1") (pintype "passive"))
    )
    (net (code "83") (name "Net-(J3-Pad10)") (class "Default")
      (node (ref "J3") (pin "10") (pinfunction "10_10") (pintype "passive"))
      (node (ref "J5") (pin "1") (pinfunction "1_1") (pintype "passive"))
    )
    (net (code "84") (name "Net-(LED1-A)") (class "Default")
      (node (ref "LED1") (pin "1") (pinfunction "A_1") (pintype "passive"))
      (node (ref "R2") (pin "2") (pinfunction "2_2") (pintype "passive"))
    )
    (net (code "85") (name "Net-(LED2-A)") (class "Default")
      (node (ref "LED2") (pin "1") (pinfunction "A_1") (pintype "passive"))
      (node (ref "R3") (pin "2") (pinfunction "2_2") (pintype "passive"))
    )
    (net (code "86") (name "Net-(P7-CC-PadA5)") (class "Default")
      (node (ref "P7") (pin "A5") (pinfunction "CC_A5") (pintype "bidirectional"))
      (node (ref "R8") (pin "2") (pinfunction "2_2") (pintype "passive"))
    )
    (net (code "87") (name "Net-(P7-CC-PadB5)") (class "Default")
      (node (ref "P7") (pin "B5") (pinfunction "CC_B5") (pintype "bidirectional"))
      (node (ref "R9") (pin "2") (pinfunction "2_2") (pintype "passive"))
    )
    (net (code "88") (name "Net-(P9-CC-PadA5)") (class "Default")
      (node (ref "P9") (pin "A5") (pinfunction "CC_A5") (pintype "bidirectional"))
      (node (ref "R10") (pin "1") (pinfunction "1_1") (pintype "passive"))
    )
    (net (code "89") (name "Net-(P9-CC-PadB5)") (class "Default")
      (node (ref "P9") (pin "B5") (pinfunction "CC_B5") (pintype "bidirectional"))
      (node (ref "R11") (pin "1") (pinfunction "1_1") (pintype "passive"))
    )
    (net (code "90") (name "Net-(PWR-A)") (class "Default")
      (node (ref "PWR") (pin "1") (pinfunction "A_1") (pintype "passive"))
      (node (ref "R1") (pin "1") (pinfunction "1_1") (pintype "passive"))
    )
    (net (code "91") (name "Net-(U1-VIN)") (class "Default")
      (node (ref "C12") (pin "1") (pinfunction "1_1") (pintype "passive"))
      (node (ref "F2") (pin "2") (pinfunction "2_2") (pintype "passive"))
      (node (ref "U1") (pin "3") (pinfunction "VIN_3") (pintype "passive"))
    )
    (net (code "92") (name "V33") (class "Default")
      (node (ref "C22") (pin "1") (pinfunction "1_1") (pintype "passive"))
      (node (ref "R16") (pin "2") (pinfunction "2_2") (pintype "passive"))
      (node (ref "U3") (pin "16") (pinfunction "V33_16") (pintype "power_in"))
    )
    (net (code "93") (name "unconnected-(J3-Pad9)") (class "Default")
      (node (ref "J3") (pin "9") (pinfunction "9_9") (pintype "passive+no_connect"))
    )
    (net (code "94") (name "unconnected-(P7-RFU1-PadA8)") (class "Default")
      (node (ref "P7") (pin "A8") (pinfunction "RFU1_A8") (pintype "bidirectional+no_connect"))
    )
    (net (code "95") (name "unconnected-(P7-RFU1-PadB8)") (class "Default")
      (node (ref "P7") (pin "B8") (pinfunction "RFU1_B8") (pintype "bidirectional+no_connect"))
    )
    (net (code "96") (name "unconnected-(P9-RFU1-PadA8)") (class "Default")
      (node (ref "P9") (pin "A8") (pinfunction "RFU1_A8") (pintype "bidirectional+no_connect"))
    )
    (net (code "97") (name "unconnected-(P9-RFU1-PadB8)") (class "Default")
      (node (ref "P9") (pin "B8") (pinfunction "RFU1_B8") (pintype "bidirectional+no_connect"))
    )
    (net (code "98") (name "unconnected-(S1-A1-Pad4)") (class "Default")
      (node (ref "S1") (pin "4") (pinfunction "A1_4") (pintype "passive"))
    )
    (net (code "99") (name "unconnected-(S1-B0-Pad2)") (class "Default")
      (node (ref "S1") (pin "2") (pinfunction "B0_2") (pintype "passive"))
    )
    (net (code "100") (name "unconnected-(S2-A1-Pad4)") (class "Default")
      (node (ref "S2") (pin "4") (pinfunction "A1_4") (pintype "passive"))
    )
    (net (code "101") (name "unconnected-(S2-B0-Pad2)") (class "Default")
      (node (ref "S2") (pin "2") (pinfunction "B0_2") (pintype "passive"))
    )
    (net (code "102") (name "unconnected-(S3-Pad2)") (class "Default")
      (node (ref "S3") (pin "2") (pinfunction "2_2") (pintype "passive"))
    )
    (net (code "103") (name "unconnected-(U3-P1.5{slash}MOSI{slash}PWM0_{slash}UCC2{slash}AIN5-Pad3)") (class "Default")
      (node (ref "U3") (pin "3") (pinfunction "P1.5/MOSI/PWM0_/UCC2/AIN5_3") (pintype "bidirectional+no_connect"))
    )
    (net (code "104") (name "unconnected-(U3-P2.2{slash}PWM3{slash}INT0_-Pad10)") (class "Default")
      (node (ref "U3") (pin "10") (pinfunction "P2.2/PWM3/INT0__10") (pintype "bidirectional+no_connect"))
    )
    (net (code "105") (name "unconnected-(U3-P2.4{slash}PWM1{slash}T2_{slash}CAP1_-Pad11)") (class "Default")
      (node (ref "U3") (pin "11") (pinfunction "P2.4/PWM1/T2_/CAP1__11") (pintype "bidirectional+no_connect"))
    )
    (net (code "106") (name "unconnected-(U3-P3.4{slash}T0-Pad9)") (class "Default")
      (node (ref "U3") (pin "9") (pinfunction "P3.4/T0_9") (pintype "bidirectional+no_connect"))
    )
    (net (code "107") (name "unconnected-(U3-P5.7{slash}RST-Pad6)") (class "Default")
      (node (ref "U3") (pin "6") (pinfunction "P5.7/RST_6") (pintype "input+no_connect"))
    )
  )
)
